# DC-DC_Bridge.net
KiCad netlist of a schematic drawn in Altium Designer
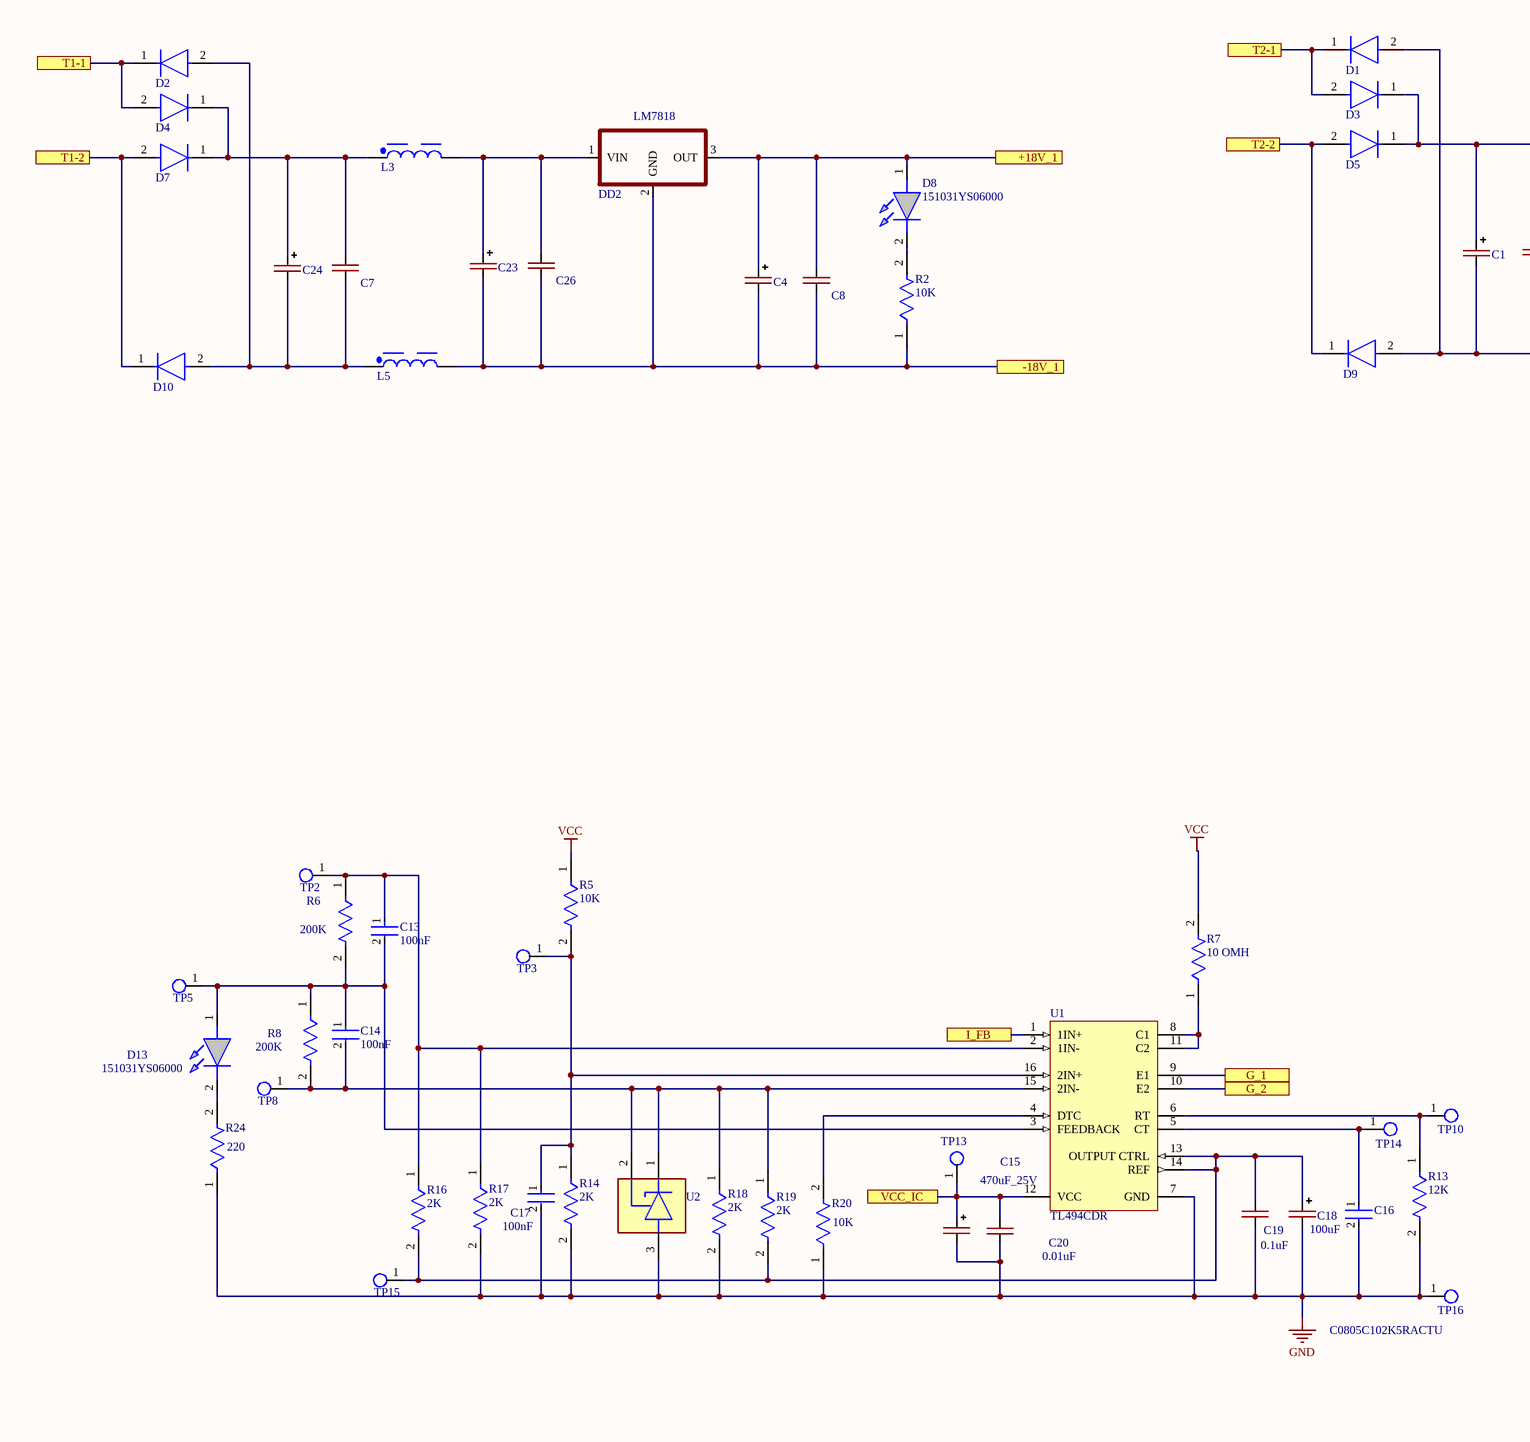
[diagram p0: DC-DC_Bridge.SchDoc, left]
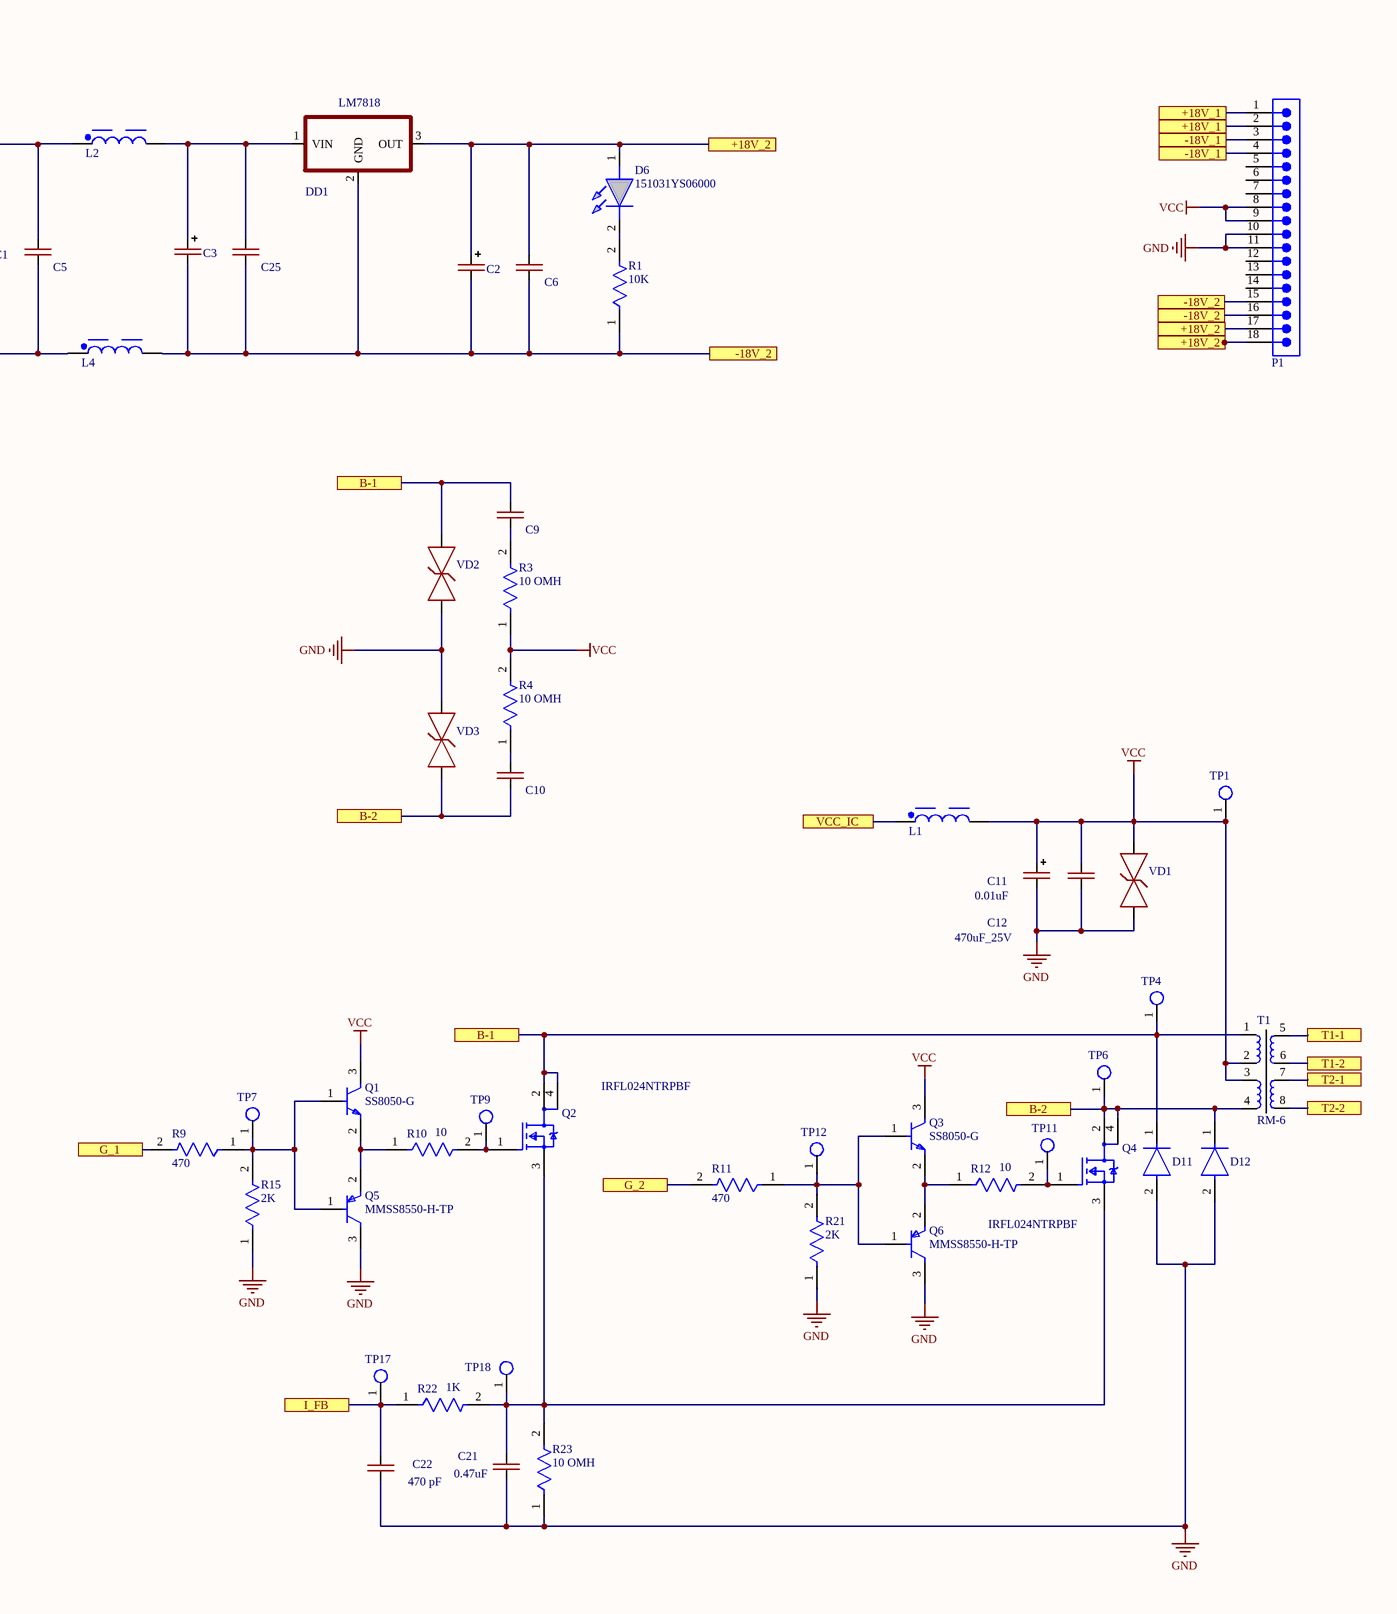
[diagram p1: DC-DC_Bridge.SchDoc, right]

(export (version "E")
  (design (tool "Eeschema 10.0.6"))
  (components
    (comp (ref "C1")
      (value "CAP-POLAR")
      (footprint "CAP_SMD_Size_G")
      (libsource (lib "PASSIVE_COMPONENTS") (part "CAP-POLAR"))
    )
    (comp (ref "C2")
      (value "CAP-POLAR")
      (footprint "CAP_SMD_Size_G")
      (libsource (lib "PASSIVE_COMPONENTS") (part "CAP-POLAR"))
    )
    (comp (ref "C3")
      (value "CAP-POLAR")
      (footprint "CAP_SMD_Size_G")
      (libsource (lib "PASSIVE_COMPONENTS") (part "CAP-POLAR"))
    )
    (comp (ref "C4")
      (value "CAP-POLAR")
      (footprint "CAP_SMD_Size_G")
      (libsource (lib "PASSIVE_COMPONENTS") (part "CAP-POLAR"))
    )
    (comp (ref "C5")
      (value "CAP-NON-POLAR")
      (footprint "CAP-0805")
      (libsource (lib "PASSIVE_COMPONENTS") (part "CAP-NON-POLAR"))
    )
    (comp (ref "C6")
      (value "CAP-NON-POLAR")
      (footprint "CAP-0805")
      (libsource (lib "PASSIVE_COMPONENTS") (part "CAP-NON-POLAR"))
    )
    (comp (ref "C7")
      (value "CAP-NON-POLAR")
      (footprint "CAP-0805")
      (libsource (lib "PASSIVE_COMPONENTS") (part "CAP-NON-POLAR"))
    )
    (comp (ref "C8")
      (value "CAP-NON-POLAR")
      (footprint "CAP-0805")
      (libsource (lib "PASSIVE_COMPONENTS") (part "CAP-NON-POLAR"))
    )
    (comp (ref "C9")
      (value "CAP-V")
      (footprint "CAP-V")
      (libsource (lib "PASSIVE_COMPONENTS") (part "CAP-V"))
    )
    (comp (ref "C10")
      (value "CAP-V")
      (footprint "CAP-V")
      (libsource (lib "PASSIVE_COMPONENTS") (part "CAP-V"))
    )
    (comp (ref "C11")
      (value "0.01uF")
      (footprint "CAP-0805")
      (libsource (lib "PASSIVE_COMPONENTS") (part "CAP-NON-POLAR"))
    )
    (comp (ref "C12")
      (value "470uF_25V")
      (footprint "CAPPOL-16x25")
      (libsource (lib "PASSIVE_COMPONENTS") (part "CAP-POLAR"))
    )
    (comp (ref "C13")
      (value "100nF")
      (footprint "FP-C0805C-DN-MFG")
      (description "CAP CER 10000PF 50V X7R 0805")
      (fields
        (field (name "MANUFACTURER PART NUMBER") "C0805C103J5RACTU")
        (field (name "MANUFACTURER") "KEMET")
      )
      (libsource (lib "Altium Content Vault") (part "b4654b650e69147ec39a6b967a45e02"))
    )
    (comp (ref "C14")
      (value "100nF")
      (footprint "FP-C0805C-DN-MFG")
      (description "CAP CER 10000PF 50V X7R 0805")
      (fields
        (field (name "MANUFACTURER PART NUMBER") "C0805C103J5RACTU")
        (field (name "MANUFACTURER") "KEMET")
      )
      (libsource (lib "Altium Content Vault") (part "b4654b650e69147ec39a6b967a45e02"))
    )
    (comp (ref "C15")
      (value "470uF_25V")
      (footprint "CAP_SMD_Size_G")
      (libsource (lib "PASSIVE_COMPONENTS") (part "CAP-POLAR"))
    )
    (comp (ref "C16")
      (value "C0805C102K5RACTU")
      (footprint "FP-C0805C-DN-MFG")
      (description "CAP CER 1000PF 50V X7R 0805")
      (fields
        (field (name "OCTOPART") "https://octopart.com/c0805c102k5ractu-kemet-93010")
        (field (name "TOLERANCE") "0.1")
      )
      (libsource (lib "Altium Content Vault") (part "b4654b650e69147ec39a6b967a45e02"))
    )
    (comp (ref "C17")
      (value "100nF")
      (footprint "FP-C0805C-DN-MFG")
      (description "CAP CER 10000PF 50V X7R 0805")
      (fields
        (field (name "MANUFACTURER PART NUMBER") "C0805C103J5RACTU")
        (field (name "MANUFACTURER") "KEMET")
      )
      (libsource (lib "Altium Content Vault") (part "b4654b650e69147ec39a6b967a45e02"))
    )
    (comp (ref "C18")
      (value "100uF")
      (footprint "CAP-TAN-D")
      (libsource (lib "PASSIVE_COMPONENTS") (part "CAP-POLAR"))
    )
    (comp (ref "C19")
      (value "0.1uF")
      (footprint "CAP-0805")
      (libsource (lib "PASSIVE_COMPONENTS") (part "CAP-NON-POLAR"))
    )
    (comp (ref "C20")
      (value "0.01uF")
      (footprint "CAP-0805")
      (libsource (lib "PASSIVE_COMPONENTS") (part "CAP-NON-POLAR"))
    )
    (comp (ref "C21")
      (value "0.47uF")
      (footprint "CAP-0805")
      (libsource (lib "PASSIVE_COMPONENTS") (part "CAP-NON-POLAR"))
    )
    (comp (ref "C22")
      (value "470 pF")
      (footprint "CAP-0805")
      (libsource (lib "PASSIVE_COMPONENTS") (part "CAP-NON-POLAR"))
    )
    (comp (ref "C23")
      (value "CAP-POLAR")
      (footprint "CAP_SMD_Size_G")
      (libsource (lib "PASSIVE_COMPONENTS") (part "CAP-POLAR"))
    )
    (comp (ref "C24")
      (value "CAP-POLAR")
      (footprint "CAP_SMD_Size_G")
      (libsource (lib "PASSIVE_COMPONENTS") (part "CAP-POLAR"))
    )
    (comp (ref "C25")
      (value "CAP-NON-POLAR")
      (footprint "CAP-0805")
      (libsource (lib "PASSIVE_COMPONENTS") (part "CAP-NON-POLAR"))
    )
    (comp (ref "C26")
      (value "CAP-NON-POLAR")
      (footprint "CAP-0805")
      (libsource (lib "PASSIVE_COMPONENTS") (part "CAP-NON-POLAR"))
    )
    (comp (ref "D1") (value "US1G") (footprint "DO-214AA") (libsource (lib "Diodes") (part "US1G")))
    (comp (ref "D2") (value "US1G") (footprint "DO-214AA") (libsource (lib "Diodes") (part "US1G")))
    (comp (ref "D3") (value "US1G") (footprint "DO-214AA") (libsource (lib "Diodes") (part "US1G")))
    (comp (ref "D4") (value "US1G") (footprint "DO-214AA") (libsource (lib "Diodes") (part "US1G")))
    (comp (ref "D5") (value "US1G") (footprint "DO-214AA") (libsource (lib "Diodes") (part "US1G")))
    (comp (ref "D6")
      (value "151031YS06000")
      (footprint "LED_RED")
      (description "WURTH ELEKTRONIK - 151031YS06000 - LED, Yellow, Through Hole, T-1 (3mm), 30 mA, 2 V, 590 nm")
      (fields (field (name "MOUSER PART NUMBER") "710-151031YS06000"))
      (libsource (lib "Optic-LED") (part "LED"))
    )
    (comp (ref "D7") (value "US1G") (footprint "DO-214AA") (libsource (lib "Diodes") (part "US1G")))
    (comp (ref "D8")
      (value "151031YS06000")
      (footprint "LED_RED")
      (description "WURTH ELEKTRONIK - 151031YS06000 - LED, Yellow, Through Hole, T-1 (3mm), 30 mA, 2 V, 590 nm")
      (fields (field (name "MOUSER PART NUMBER") "710-151031YS06000"))
      (libsource (lib "Optic-LED") (part "LED"))
    )
    (comp (ref "D9") (value "US1G") (footprint "DO-214AA") (libsource (lib "Diodes") (part "US1G")))
    (comp (ref "D10") (value "US1G") (footprint "DO-214AA") (libsource (lib "Diodes") (part "US1G")))
    (comp (ref "D11") (value "US1G") (footprint "DO-214AA") (libsource (lib "Diodes") (part "US1G")))
    (comp (ref "D12") (value "US1G") (footprint "DO-214AA") (libsource (lib "Diodes") (part "US1G")))
    (comp (ref "D13")
      (value "151031YS06000")
      (footprint "LED_RED")
      (description "WURTH ELEKTRONIK - 151031YS06000 - LED, Yellow, Through Hole, T-1 (3mm), 30 mA, 2 V, 590 nm")
      (fields (field (name "MOUSER PART NUMBER") "710-151031YS06000"))
      (libsource (lib "Optic-LED") (part "LED"))
    )
    (comp (ref "DD1")
      (value "LM7818")
      (footprint "TO-252")
      (libsource (lib "LM7818__TO-252") (part "LM7818"))
    )
    (comp (ref "DD2")
      (value "LM7818")
      (footprint "TO-252")
      (libsource (lib "LM7818__TO-252") (part "LM7818"))
    )
    (comp (ref "L1")
      (value "390µH, 0.38A")
      (footprint "WE-PD2_7850")
      (description "WE-PD2 SMT Power Inductor, size 7850, 390µH, 0.38A, 1.77Ω")
      (fields
        (field (name "MANUFACTURER PART NUMBER") "744775239")
        (field (name "MANUFACTURER") "Wurth Elektronik")
      )
      (libsource (lib "WE-PD2 (rev22d)") (part "744775239"))
    )
    (comp (ref "L2")
      (value "390µH, 0.38A")
      (footprint "WE-PD2_7850")
      (description "WE-PD2 SMT Power Inductor, size 7850, 390µH, 0.38A, 1.77Ω")
      (fields
        (field (name "MANUFACTURER PART NUMBER") "744775239")
        (field (name "MANUFACTURER") "Wurth Elektronik")
      )
      (libsource (lib "WE-PD2 (rev22d)") (part "744775239"))
    )
    (comp (ref "L3")
      (value "390µH, 0.38A")
      (footprint "WE-PD2_7850")
      (description "WE-PD2 SMT Power Inductor, size 7850, 390µH, 0.38A, 1.77Ω")
      (fields
        (field (name "MANUFACTURER PART NUMBER") "744775239")
        (field (name "MANUFACTURER") "Wurth Elektronik")
      )
      (libsource (lib "WE-PD2 (rev22d)") (part "744775239"))
    )
    (comp (ref "L4")
      (value "390µH, 0.38A")
      (footprint "WE-PD2_7850")
      (description "WE-PD2 SMT Power Inductor, size 7850, 390µH, 0.38A, 1.77Ω")
      (fields
        (field (name "MANUFACTURER PART NUMBER") "744775239")
        (field (name "MANUFACTURER") "Wurth Elektronik")
      )
      (libsource (lib "WE-PD2 (rev22d)") (part "744775239"))
    )
    (comp (ref "L5")
      (value "390µH, 0.38A")
      (footprint "WE-PD2_7850")
      (description "WE-PD2 SMT Power Inductor, size 7850, 390µH, 0.38A, 1.77Ω")
      (fields
        (field (name "MANUFACTURER PART NUMBER") "744775239")
        (field (name "MANUFACTURER") "Wurth Elektronik")
      )
      (libsource (lib "WE-PD2 (rev22d)") (part "744775239"))
    )
    (comp (ref "P1")
      (value "61301811021")
      (footprint "61301811021")
      (description "WR-PHD Pin Header, THT, Angled, pitch 2.54mm, 1 Row, 18P")
      (fields (field (name "MANUFACTURER") "Wurth Elektronik"))
      (libsource (lib "Altium_WR-PHD (rev22b)") (part "61301811021"))
    )
    (comp (ref "Q1")
      (value "SS8050-G")
      (footprint "FP-SS8050-G-MFG")
      (description "NPN TRANSISTOR 1.5A 40V SOT-23 R")
      (libsource (lib "Altium Content Vault") (part "2a1388f82443b098dcd57d24ac7632d"))
    )
    (comp (ref "Q2")
      (value "IRFL024NTRPBF")
      (footprint "FP-PG-SOT223-3-IPC_B")
      (description "MOSFET N-CH 55V 2.8A SOT223")
      (libsource (lib "Altium Content Vault") (part "7f70c8421781a2c4d0598199639518f"))
    )
    (comp (ref "Q3")
      (value "SS8050-G")
      (footprint "FP-SS8050-G-MFG")
      (description "NPN TRANSISTOR 1.5A 40V SOT-23 R")
      (libsource (lib "Altium Content Vault") (part "2a1388f82443b098dcd57d24ac7632d"))
    )
    (comp (ref "Q4")
      (value "IRFL024NTRPBF")
      (footprint "FP-PG-SOT223-3-IPC_B")
      (description "MOSFET N-CH 55V 2.8A SOT223")
      (libsource (lib "Altium Content Vault") (part "7f70c8421781a2c4d0598199639518f"))
    )
    (comp (ref "Q5")
      (value "MMSS8550-H-TP")
      (footprint "FP-SOT-23-IPC_B")
      (description "TRANS PNP 25V 1.5A SOT23")
      (libsource (lib "Altium Content Vault") (part "0e8486ed3b47d9c69b8404ba87cf0f7"))
    )
    (comp (ref "Q6")
      (value "MMSS8550-H-TP")
      (footprint "FP-SOT-23-IPC_B")
      (description "TRANS PNP 25V 1.5A SOT23")
      (libsource (lib "Altium Content Vault") (part "0e8486ed3b47d9c69b8404ba87cf0f7"))
    )
    (comp (ref "R1")
      (value "10K")
      (footprint "RES-0805")
      (libsource (lib "PASSIVE_COMPONENTS") (part "RES-CONST"))
    )
    (comp (ref "R2")
      (value "10K")
      (footprint "RES-0805")
      (libsource (lib "PASSIVE_COMPONENTS") (part "RES-CONST"))
    )
    (comp (ref "R3")
      (value "10 OMH")
      (footprint "RES-1206")
      (libsource (lib "PASSIVE_COMPONENTS") (part "RES-CONST"))
    )
    (comp (ref "R4")
      (value "10 OMH")
      (footprint "RES-1206")
      (libsource (lib "PASSIVE_COMPONENTS") (part "RES-CONST"))
    )
    (comp (ref "R5")
      (value "10K")
      (footprint "FP-CRCW0805-e3-MFG")
      (description "RES Thick Film, 2kΩ, 1%, 0.125W, 100ppm/°C, 0805")
      (fields (field (name "TOLERANCE") "1%"))
      (libsource (lib "Pasive_components") (part "CMP-2001-04908-2"))
    )
    (comp (ref "R6")
      (value "200K")
      (footprint "FP-CRCW0805-e3-MFG")
      (description "RES Thick Film, 2kΩ, 1%, 0.125W, 100ppm/°C, 0805")
      (fields (field (name "TOLERANCE") "1%"))
      (libsource (lib "Pasive_components") (part "CMP-2001-04908-2"))
    )
    (comp (ref "R7")
      (value "10 OMH")
      (footprint "RES-1206")
      (libsource (lib "PASSIVE_COMPONENTS") (part "RES-CONST"))
    )
    (comp (ref "R8")
      (value "200K")
      (footprint "FP-CRCW0805-e3-MFG")
      (description "RES Thick Film, 2kΩ, 1%, 0.125W, 100ppm/°C, 0805")
      (fields (field (name "TOLERANCE") "1%"))
      (libsource (lib "Pasive_components") (part "CMP-2001-04908-2"))
    )
    (comp (ref "R9")
      (value "470")
      (footprint "RES-0805")
      (libsource (lib "PASSIVE_COMPONENTS") (part "RES-CONST"))
    )
    (comp (ref "R10")
      (value "10")
      (footprint "RES-0805")
      (libsource (lib "PASSIVE_COMPONENTS") (part "RES-CONST"))
    )
    (comp (ref "R11")
      (value "470")
      (footprint "RES-0805")
      (libsource (lib "PASSIVE_COMPONENTS") (part "RES-CONST"))
    )
    (comp (ref "R12")
      (value "10")
      (footprint "RES-0805")
      (libsource (lib "PASSIVE_COMPONENTS") (part "RES-CONST"))
    )
    (comp (ref "R13")
      (value "12K")
      (footprint "FP-CRCW0805-e3-MFG")
      (description "RES Thick Film, 12kΩ, 1%, 0.125W, 100ppm/°C, 0805")
      (fields (field (name "TOLERANCE") "1%"))
      (libsource (lib "Pasive_components") (part "CMP-2001-04908-2"))
    )
    (comp (ref "R14")
      (value "2K")
      (footprint "FP-CRCW0805-e3-MFG")
      (description "RES Thick Film, 2kΩ, 1%, 0.125W, 100ppm/°C, 0805")
      (fields (field (name "TOLERANCE") "1%"))
      (libsource (lib "Pasive_components") (part "CMP-2001-04908-2"))
    )
    (comp (ref "R15")
      (value "2K")
      (footprint "RES-0805")
      (libsource (lib "PASSIVE_COMPONENTS") (part "RES-CONST"))
    )
    (comp (ref "R16")
      (value "2K")
      (footprint "FP-CRCW0805-e3-MFG")
      (description "RES Thick Film, 2kΩ, 1%, 0.125W, 100ppm/°C, 0805")
      (fields (field (name "TOLERANCE") "1%"))
      (libsource (lib "Pasive_components") (part "CMP-2001-04908-2"))
    )
    (comp (ref "R17")
      (value "2K")
      (footprint "FP-CRCW0805-e3-MFG")
      (description "RES Thick Film, 82kΩ, 1%, 0.125W, 100ppm/°C, 0805")
      (fields (field (name "TOLERANCE") "1%"))
      (libsource (lib "Pasive_components") (part "CMP-2001-04908-2"))
    )
    (comp (ref "R18")
      (value "2K")
      (footprint "FP-CRCW0805-e3-MFG")
      (description "RES Thick Film, 2kΩ, 1%, 0.125W, 100ppm/°C, 0805")
      (fields (field (name "TOLERANCE") "1%"))
      (libsource (lib "Pasive_components") (part "CMP-2001-04908-2"))
    )
    (comp (ref "R19")
      (value "2K")
      (footprint "FP-CRCW0805-e3-MFG")
      (description "RES Thick Film, 2kΩ, 1%, 0.125W, 100ppm/°C, 0805")
      (fields (field (name "TOLERANCE") "1%"))
      (libsource (lib "Pasive_components") (part "CMP-2001-04908-2"))
    )
    (comp (ref "R20")
      (value "10K")
      (footprint "RES-0805")
      (libsource (lib "PASSIVE_COMPONENTS") (part "RES-CONST"))
    )
    (comp (ref "R21")
      (value "2K")
      (footprint "RES-0805")
      (libsource (lib "PASSIVE_COMPONENTS") (part "RES-CONST"))
    )
    (comp (ref "R22")
      (value "1K")
      (footprint "RES-0805")
      (libsource (lib "PASSIVE_COMPONENTS") (part "RES-CONST"))
    )
    (comp (ref "R23")
      (value "10 OMH")
      (footprint "RES-2512")
      (libsource (lib "PASSIVE_COMPONENTS") (part "RES-CONST"))
    )
    (comp (ref "R24")
      (value "220")
      (footprint "RES-0805")
      (libsource (lib "PASSIVE_COMPONENTS") (part "RES-CONST"))
    )
    (comp (ref "T1")
      (value "RM-6")
      (footprint "TRANS_RM6")
      (libsource (lib "Transformers") (part "RM_6_12-12-18-18"))
    )
    (comp (ref "TP1")
      (value "~")
      (footprint "Test_Point")
      (description "Test_Point")
      (libsource (lib "Connectors") (part "TP_PCB?"))
    )
    (comp (ref "TP2")
      (value "Test_Point_PCB")
      (footprint "Test_Point")
      (description "Test_Point")
      (libsource (lib "Test_Point") (part "TP_PCB?"))
    )
    (comp (ref "TP3")
      (value "Test_Point_PCB")
      (footprint "Test_Point")
      (description "Test_Point")
      (libsource (lib "Test_Point") (part "TP_PCB?"))
    )
    (comp (ref "TP4")
      (value "~")
      (footprint "Test_Point")
      (description "Test_Point")
      (libsource (lib "Connectors") (part "TP_PCB?"))
    )
    (comp (ref "TP5")
      (value "Test_Point_PCB")
      (footprint "Test_Point")
      (description "Test_Point")
      (libsource (lib "Test_Point") (part "TP_PCB?"))
    )
    (comp (ref "TP6")
      (value "~")
      (footprint "Test_Point")
      (description "Test_Point")
      (libsource (lib "Connectors") (part "TP_PCB?"))
    )
    (comp (ref "TP7")
      (value "~")
      (footprint "Test_Point")
      (description "Test_Point")
      (libsource (lib "Connectors") (part "TP_PCB?"))
    )
    (comp (ref "TP8")
      (value "~")
      (footprint "Test_Point")
      (description "Test_Point")
      (libsource (lib "Connectors") (part "TP_PCB?"))
    )
    (comp (ref "TP9")
      (value "~")
      (footprint "Test_Point")
      (description "Test_Point")
      (libsource (lib "Connectors") (part "TP_PCB?"))
    )
    (comp (ref "TP10")
      (value "~")
      (footprint "Test_Point")
      (description "Test_Point")
      (libsource (lib "Connectors") (part "TP_PCB?"))
    )
    (comp (ref "TP11")
      (value "~")
      (footprint "Test_Point")
      (description "Test_Point")
      (libsource (lib "Connectors") (part "TP_PCB?"))
    )
    (comp (ref "TP12")
      (value "~")
      (footprint "Test_Point")
      (description "Test_Point")
      (libsource (lib "Connectors") (part "TP_PCB?"))
    )
    (comp (ref "TP13")
      (value "~")
      (footprint "Test_Point")
      (description "Test_Point")
      (libsource (lib "Connectors") (part "TP_PCB?"))
    )
    (comp (ref "TP14")
      (value "Test_Point_PCB")
      (footprint "Test_Point")
      (description "Test_Point")
      (libsource (lib "Test_Point") (part "TP_PCB?"))
    )
    (comp (ref "TP15")
      (value "Test_Point_PCB")
      (footprint "Test_Point")
      (description "Test_Point")
      (libsource (lib "Test_Point") (part "TP_PCB?"))
    )
    (comp (ref "TP16")
      (value "~")
      (footprint "Test_Point")
      (description "Test_Point")
      (libsource (lib "Connectors") (part "TP_PCB?"))
    )
    (comp (ref "TP17")
      (value "~")
      (footprint "Test_Point")
      (description "Test_Point")
      (libsource (lib "Connectors") (part "TP_PCB?"))
    )
    (comp (ref "TP18")
      (value "~")
      (footprint "Test_Point")
      (description "Test_Point")
      (libsource (lib "Connectors") (part "TP_PCB?"))
    )
    (comp (ref "U1")
      (value "TL494CDR")
      (footprint "D0016A_N")
      (fields (field (name "MANUFACTURER") "Texas Instruments"))
      (libsource (lib "Altium Content Vault") (part "TI-494D16"))
    )
    (comp (ref "U2")
      (value "TL431")
      (footprint "TL431_SOT-23-3(A)")
      (description "TL431_SOT-23-3")
      (libsource (lib "Diodes") (part "TL431_SOT-23-3"))
    )
    (comp (ref "VD1")
      (value "Suppressor")
      (footprint "DO-214AA")
      (libsource (lib "Diodes") (part "Suppressor"))
    )
    (comp (ref "VD2")
      (value "Suppressor")
      (footprint "P6KE350CA")
      (libsource (lib "Diodes") (part "Suppressor"))
    )
    (comp (ref "VD3")
      (value "Suppressor")
      (footprint "P6KE350CA")
      (libsource (lib "Diodes") (part "Suppressor"))
    )
  )
  (nets
    (net (code "1") (name "/+18V_1") (class "Default")
      (node (ref "C4") (pin "1") (pinfunction "+_1") (pintype "passive"))
      (node (ref "C8") (pin "2") (pinfunction "2_2") (pintype "passive"))
      (node (ref "D8") (pin "1") (pinfunction "A_1") (pintype "passive"))
      (node (ref "DD2") (pin "3") (pinfunction "OUT_3") (pintype "passive"))
      (node (ref "P1") (pin "1") (pinfunction "1_1") (pintype "passive"))
      (node (ref "P1") (pin "2") (pinfunction "2_2") (pintype "passive"))
    )
    (net (code "2") (name "/+18V_2") (class "Default")
      (node (ref "C2") (pin "1") (pinfunction "+_1") (pintype "passive"))
      (node (ref "C6") (pin "2") (pinfunction "2_2") (pintype "passive"))
      (node (ref "D6") (pin "1") (pinfunction "A_1") (pintype "passive"))
      (node (ref "DD1") (pin "3") (pinfunction "OUT_3") (pintype "passive"))
      (node (ref "P1") (pin "17") (pinfunction "17_17") (pintype "passive"))
      (node (ref "P1") (pin "18") (pinfunction "18_18") (pintype "passive"))
    )
    (net (code "3") (name "/-18V_1") (class "Default")
      (node (ref "C23") (pin "2") (pinfunction "-_2") (pintype "passive"))
      (node (ref "C26") (pin "1") (pinfunction "1_1") (pintype "passive"))
      (node (ref "C4") (pin "2") (pinfunction "-_2") (pintype "passive"))
      (node (ref "C8") (pin "1") (pinfunction "1_1") (pintype "passive"))
      (node (ref "DD2") (pin "2") (pinfunction "GND_2") (pintype "passive"))
      (node (ref "L5") (pin "2") (pinfunction "2_2") (pintype "passive"))
      (node (ref "P1") (pin "3") (pinfunction "3_3") (pintype "passive"))
      (node (ref "P1") (pin "4") (pinfunction "4_4") (pintype "passive"))
      (node (ref "R2") (pin "1") (pinfunction "1_1") (pintype "passive"))
    )
    (net (code "4") (name "/-18V_2") (class "Default")
      (node (ref "C2") (pin "2") (pinfunction "-_2") (pintype "passive"))
      (node (ref "C25") (pin "1") (pinfunction "1_1") (pintype "passive"))
      (node (ref "C3") (pin "2") (pinfunction "-_2") (pintype "passive"))
      (node (ref "C6") (pin "1") (pinfunction "1_1") (pintype "passive"))
      (node (ref "DD1") (pin "2") (pinfunction "GND_2") (pintype "passive"))
      (node (ref "L4") (pin "2") (pinfunction "2_2") (pintype "passive"))
      (node (ref "P1") (pin "15") (pinfunction "15_15") (pintype "passive"))
      (node (ref "P1") (pin "16") (pinfunction "16_16") (pintype "passive"))
      (node (ref "R1") (pin "1") (pinfunction "1_1") (pintype "passive"))
    )
    (net (code "5") (name "/B-1") (class "Default")
      (node (ref "C9") (pin "2") (pinfunction "2_2") (pintype "passive"))
      (node (ref "D11") (pin "1") (pinfunction "C_1") (pintype "passive"))
      (node (ref "Q2") (pin "2") (pinfunction "D_2") (pintype "passive"))
      (node (ref "Q2") (pin "4") (pinfunction "D_4") (pintype "passive"))
      (node (ref "T1") (pin "1") (pinfunction "1_1") (pintype "passive"))
      (node (ref "TP4") (pin "1") (pinfunction "G9_1") (pintype "passive"))
      (node (ref "VD2") (pin "2") (pinfunction "A_2") (pintype "passive"))
    )
    (net (code "6") (name "/B-2") (class "Default")
      (node (ref "C10") (pin "1") (pinfunction "1_1") (pintype "passive"))
      (node (ref "D12") (pin "1") (pinfunction "C_1") (pintype "passive"))
      (node (ref "Q4") (pin "2") (pinfunction "D_2") (pintype "passive"))
      (node (ref "Q4") (pin "4") (pinfunction "D_4") (pintype "passive"))
      (node (ref "T1") (pin "4") (pinfunction "4_4") (pintype "passive"))
      (node (ref "TP6") (pin "1") (pinfunction "G9_1") (pintype "passive"))
      (node (ref "VD3") (pin "1") (pinfunction "C_1") (pintype "passive"))
    )
    (net (code "7") (name "/G_1") (class "Default")
      (node (ref "R9") (pin "2") (pinfunction "2_2") (pintype "passive"))
      (node (ref "U1") (pin "9") (pinfunction "E1_9") (pintype "passive"))
    )
    (net (code "8") (name "/G_2") (class "Default")
      (node (ref "R11") (pin "2") (pinfunction "2_2") (pintype "passive"))
      (node (ref "U1") (pin "10") (pinfunction "E2_10") (pintype "passive"))
    )
    (net (code "9") (name "/I_FB") (class "Default")
      (node (ref "C22") (pin "2") (pinfunction "2_2") (pintype "passive"))
      (node (ref "R22") (pin "1") (pinfunction "1_1") (pintype "passive"))
      (node (ref "TP17") (pin "1") (pinfunction "G9_1") (pintype "passive"))
      (node (ref "U1") (pin "1") (pinfunction "1IN+_1") (pintype "input"))
    )
    (net (code "10") (name "/T1-1") (class "Default")
      (node (ref "D2") (pin "1") (pinfunction "C_1") (pintype "passive"))
      (node (ref "D4") (pin "2") (pinfunction "A_2") (pintype "passive"))
      (node (ref "T1") (pin "5") (pinfunction "5_5") (pintype "passive"))
    )
    (net (code "11") (name "/T1-2") (class "Default")
      (node (ref "D10") (pin "1") (pinfunction "C_1") (pintype "passive"))
      (node (ref "D7") (pin "2") (pinfunction "A_2") (pintype "passive"))
      (node (ref "T1") (pin "6") (pinfunction "6_6") (pintype "passive"))
    )
    (net (code "12") (name "/T2-1") (class "Default")
      (node (ref "D1") (pin "1") (pinfunction "C_1") (pintype "passive"))
      (node (ref "D3") (pin "2") (pinfunction "A_2") (pintype "passive"))
      (node (ref "T1") (pin "7") (pinfunction "7_7") (pintype "passive"))
    )
    (net (code "13") (name "/T2-2") (class "Default")
      (node (ref "D5") (pin "2") (pinfunction "A_2") (pintype "passive"))
      (node (ref "D9") (pin "1") (pinfunction "C_1") (pintype "passive"))
      (node (ref "T1") (pin "8") (pinfunction "8_8") (pintype "passive"))
    )
    (net (code "14") (name "/VCC_IC") (class "Default")
      (node (ref "C15") (pin "1") (pinfunction "+_1") (pintype "passive"))
      (node (ref "C20") (pin "2") (pinfunction "2_2") (pintype "passive"))
      (node (ref "L1") (pin "1") (pinfunction "1_1") (pintype "passive"))
      (node (ref "TP13") (pin "1") (pinfunction "G9_1") (pintype "passive"))
      (node (ref "U1") (pin "12") (pinfunction "VCC_12") (pintype "power_in"))
    )
    (net (code "15") (name "GND") (class "Default")
      (node (ref "C11") (pin "1") (pinfunction "1_1") (pintype "passive"))
      (node (ref "C12") (pin "2") (pinfunction "-_2") (pintype "passive"))
      (node (ref "C15") (pin "2") (pinfunction "-_2") (pintype "passive"))
      (node (ref "C16") (pin "2") (pinfunction "2_2") (pintype "passive"))
      (node (ref "C17") (pin "2") (pinfunction "2_2") (pintype "passive"))
      (node (ref "C18") (pin "2") (pinfunction "-_2") (pintype "passive"))
      (node (ref "C19") (pin "1") (pinfunction "1_1") (pintype "passive"))
      (node (ref "C20") (pin "1") (pinfunction "1_1") (pintype "passive"))
      (node (ref "C21") (pin "1") (pinfunction "1_1") (pintype "passive"))
      (node (ref "C22") (pin "1") (pinfunction "1_1") (pintype "passive"))
      (node (ref "D11") (pin "2") (pinfunction "A_2") (pintype "passive"))
      (node (ref "D12") (pin "2") (pinfunction "A_2") (pintype "passive"))
      (node (ref "P1") (pin "10") (pinfunction "10_10") (pintype "passive"))
      (node (ref "P1") (pin "11") (pinfunction "11_11") (pintype "passive"))
      (node (ref "Q5") (pin "3") (pinfunction "C_3") (pintype "passive"))
      (node (ref "Q6") (pin "3") (pinfunction "C_3") (pintype "passive"))
      (node (ref "R13") (pin "2") (pinfunction "2_2") (pintype "passive"))
      (node (ref "R14") (pin "2") (pinfunction "2_2") (pintype "passive"))
      (node (ref "R15") (pin "1") (pinfunction "1_1") (pintype "passive"))
      (node (ref "R17") (pin "2") (pinfunction "2_2") (pintype "passive"))
      (node (ref "R18") (pin "2") (pinfunction "2_2") (pintype "passive"))
      (node (ref "R20") (pin "1") (pinfunction "1_1") (pintype "passive"))
      (node (ref "R21") (pin "1") (pinfunction "1_1") (pintype "passive"))
      (node (ref "R23") (pin "1") (pinfunction "1_1") (pintype "passive"))
      (node (ref "R24") (pin "1") (pinfunction "1_1") (pintype "passive"))
      (node (ref "TP16") (pin "1") (pinfunction "G9_1") (pintype "passive"))
      (node (ref "U1") (pin "7") (pinfunction "GND_7") (pintype "power_in"))
      (node (ref "U2") (pin "3") (pinfunction "A_3") (pintype "passive"))
      (node (ref "VD1") (pin "1") (pinfunction "C_1") (pintype "passive"))
      (node (ref "VD2") (pin "1") (pinfunction "C_1") (pintype "passive"))
      (node (ref "VD3") (pin "2") (pinfunction "A_2") (pintype "passive"))
    )
    (net (code "16") (name "Net-(C1-+)") (class "Default")
      (node (ref "C1") (pin "1") (pinfunction "+_1") (pintype "passive"))
      (node (ref "C5") (pin "2") (pinfunction "2_2") (pintype "passive"))
      (node (ref "D3") (pin "1") (pinfunction "C_1") (pintype "passive"))
      (node (ref "D5") (pin "1") (pinfunction "C_1") (pintype "passive"))
      (node (ref "L2") (pin "1") (pinfunction "1_1") (pintype "passive"))
    )
    (net (code "17") (name "Net-(C1--)") (class "Default")
      (node (ref "C1") (pin "2") (pinfunction "-_2") (pintype "passive"))
      (node (ref "C5") (pin "1") (pinfunction "1_1") (pintype "passive"))
      (node (ref "D1") (pin "2") (pinfunction "A_2") (pintype "passive"))
      (node (ref "D9") (pin "2") (pinfunction "A_2") (pintype "passive"))
      (node (ref "L4") (pin "1") (pinfunction "1_1") (pintype "passive"))
    )
    (net (code "18") (name "Net-(C3-+)") (class "Default")
      (node (ref "C25") (pin "2") (pinfunction "2_2") (pintype "passive"))
      (node (ref "C3") (pin "1") (pinfunction "+_1") (pintype "passive"))
      (node (ref "DD1") (pin "1") (pinfunction "VIN_1") (pintype "passive"))
      (node (ref "L2") (pin "2") (pinfunction "2_2") (pintype "passive"))
    )
    (net (code "19") (name "Net-(C9-Pad1)") (class "Default")
      (node (ref "C9") (pin "1") (pinfunction "1_1") (pintype "passive"))
      (node (ref "R3") (pin "2") (pinfunction "2_2") (pintype "passive"))
    )
    (net (code "20") (name "Net-(C10-Pad2)") (class "Default")
      (node (ref "C10") (pin "2") (pinfunction "2_2") (pintype "passive"))
      (node (ref "R4") (pin "1") (pinfunction "1_1") (pintype "passive"))
    )
    (net (code "21") (name "Net-(C18-+)") (class "Default")
      (node (ref "C18") (pin "1") (pinfunction "+_1") (pintype "passive"))
      (node (ref "C19") (pin "2") (pinfunction "2_2") (pintype "passive"))
      (node (ref "R16") (pin "2") (pinfunction "2_2") (pintype "passive"))
      (node (ref "R19") (pin "2") (pinfunction "2_2") (pintype "passive"))
      (node (ref "TP15") (pin "1") (pinfunction "G9_1") (pintype "passive"))
      (node (ref "U1") (pin "13") (pinfunction "OUTPUT_CTRL_13") (pintype "input"))
      (node (ref "U1") (pin "14") (pinfunction "REF_14") (pintype "output"))
    )
    (net (code "22") (name "Net-(C23-+)") (class "Default")
      (node (ref "C23") (pin "1") (pinfunction "+_1") (pintype "passive"))
      (node (ref "C26") (pin "2") (pinfunction "2_2") (pintype "passive"))
      (node (ref "DD2") (pin "1") (pinfunction "VIN_1") (pintype "passive"))
      (node (ref "L3") (pin "2") (pinfunction "2_2") (pintype "passive"))
    )
    (net (code "23") (name "Net-(C24-+)") (class "Default")
      (node (ref "C24") (pin "1") (pinfunction "+_1") (pintype "passive"))
      (node (ref "C7") (pin "2") (pinfunction "2_2") (pintype "passive"))
      (node (ref "D4") (pin "1") (pinfunction "C_1") (pintype "passive"))
      (node (ref "D7") (pin "1") (pinfunction "C_1") (pintype "passive"))
      (node (ref "L3") (pin "1") (pinfunction "1_1") (pintype "passive"))
    )
    (net (code "24") (name "Net-(C24--)") (class "Default")
      (node (ref "C24") (pin "2") (pinfunction "-_2") (pintype "passive"))
      (node (ref "C7") (pin "1") (pinfunction "1_1") (pintype "passive"))
      (node (ref "D10") (pin "2") (pinfunction "A_2") (pintype "passive"))
      (node (ref "D2") (pin "2") (pinfunction "A_2") (pintype "passive"))
      (node (ref "L5") (pin "1") (pinfunction "1_1") (pintype "passive"))
    )
    (net (code "25") (name "Net-(D6-K)") (class "Default")
      (node (ref "D6") (pin "2") (pinfunction "K_2") (pintype "passive"))
      (node (ref "R1") (pin "2") (pinfunction "2_2") (pintype "passive"))
    )
    (net (code "26") (name "Net-(D8-K)") (class "Default")
      (node (ref "D8") (pin "2") (pinfunction "K_2") (pintype "passive"))
      (node (ref "R2") (pin "2") (pinfunction "2_2") (pintype "passive"))
    )
    (net (code "27") (name "Net-(D13-A)") (class "Default")
      (node (ref "C13") (pin "2") (pinfunction "2_2") (pintype "passive"))
      (node (ref "C14") (pin "1") (pinfunction "1_1") (pintype "passive"))
      (node (ref "D13") (pin "1") (pinfunction "A_1") (pintype "passive"))
      (node (ref "R6") (pin "2") (pinfunction "2_2") (pintype "passive"))
      (node (ref "R8") (pin "1") (pinfunction "1_1") (pintype "passive"))
      (node (ref "TP5") (pin "1") (pinfunction "G9_1") (pintype "passive"))
      (node (ref "U1") (pin "3") (pinfunction "FEEDBACK_3") (pintype "input"))
    )
    (net (code "28") (name "Net-(D13-K)") (class "Default")
      (node (ref "D13") (pin "2") (pinfunction "K_2") (pintype "passive"))
      (node (ref "R24") (pin "2") (pinfunction "2_2") (pintype "passive"))
    )
    (net (code "29") (name "Net-(Q1-B)") (class "Default")
      (node (ref "Q1") (pin "1") (pinfunction "B_1") (pintype "passive"))
      (node (ref "Q5") (pin "1") (pinfunction "B_1") (pintype "passive"))
      (node (ref "R15") (pin "2") (pinfunction "2_2") (pintype "passive"))
      (node (ref "R9") (pin "1") (pinfunction "1_1") (pintype "passive"))
      (node (ref "TP7") (pin "1") (pinfunction "G9_1") (pintype "passive"))
    )
    (net (code "30") (name "Net-(Q1-E)") (class "Default")
      (node (ref "Q1") (pin "2") (pinfunction "E_2") (pintype "passive"))
      (node (ref "Q5") (pin "2") (pinfunction "E_2") (pintype "passive"))
      (node (ref "R10") (pin "1") (pinfunction "1_1") (pintype "passive"))
    )
    (net (code "31") (name "Net-(Q2-G)") (class "Default")
      (node (ref "Q2") (pin "1") (pinfunction "G_1") (pintype "passive"))
      (node (ref "R10") (pin "2") (pinfunction "2_2") (pintype "passive"))
      (node (ref "TP9") (pin "1") (pinfunction "G9_1") (pintype "passive"))
    )
    (net (code "32") (name "Net-(Q2-S)") (class "Default")
      (node (ref "C21") (pin "2") (pinfunction "2_2") (pintype "passive"))
      (node (ref "Q2") (pin "3") (pinfunction "S_3") (pintype "passive"))
      (node (ref "Q4") (pin "3") (pinfunction "S_3") (pintype "passive"))
      (node (ref "R22") (pin "2") (pinfunction "2_2") (pintype "passive"))
      (node (ref "R23") (pin "2") (pinfunction "2_2") (pintype "passive"))
      (node (ref "TP18") (pin "1") (pinfunction "G9_1") (pintype "passive"))
    )
    (net (code "33") (name "Net-(Q3-B)") (class "Default")
      (node (ref "Q3") (pin "1") (pinfunction "B_1") (pintype "passive"))
      (node (ref "Q6") (pin "1") (pinfunction "B_1") (pintype "passive"))
      (node (ref "R11") (pin "1") (pinfunction "1_1") (pintype "passive"))
      (node (ref "R21") (pin "2") (pinfunction "2_2") (pintype "passive"))
      (node (ref "TP12") (pin "1") (pinfunction "G9_1") (pintype "passive"))
    )
    (net (code "34") (name "Net-(Q3-E)") (class "Default")
      (node (ref "Q3") (pin "2") (pinfunction "E_2") (pintype "passive"))
      (node (ref "Q6") (pin "2") (pinfunction "E_2") (pintype "passive"))
      (node (ref "R12") (pin "1") (pinfunction "1_1") (pintype "passive"))
    )
    (net (code "35") (name "Net-(Q4-G)") (class "Default")
      (node (ref "Q4") (pin "1") (pinfunction "G_1") (pintype "passive"))
      (node (ref "R12") (pin "2") (pinfunction "2_2") (pintype "passive"))
      (node (ref "TP11") (pin "1") (pinfunction "G9_1") (pintype "passive"))
    )
    (net (code "36") (name "Net-(TP2-G9)") (class "Default")
      (node (ref "C13") (pin "1") (pinfunction "1_1") (pintype "passive"))
      (node (ref "R16") (pin "1") (pinfunction "1_1") (pintype "passive"))
      (node (ref "R17") (pin "1") (pinfunction "1_1") (pintype "passive"))
      (node (ref "R6") (pin "1") (pinfunction "1_1") (pintype "passive"))
      (node (ref "TP2") (pin "1") (pinfunction "G9_1") (pintype "passive"))
      (node (ref "U1") (pin "2") (pinfunction "1IN-_2") (pintype "input"))
    )
    (net (code "37") (name "Net-(TP3-G9)") (class "Default")
      (node (ref "C17") (pin "1") (pinfunction "1_1") (pintype "passive"))
      (node (ref "R14") (pin "1") (pinfunction "1_1") (pintype "passive"))
      (node (ref "R5") (pin "2") (pinfunction "2_2") (pintype "passive"))
      (node (ref "TP3") (pin "1") (pinfunction "G9_1") (pintype "passive"))
      (node (ref "U1") (pin "16") (pinfunction "2IN+_16") (pintype "input"))
    )
    (net (code "38") (name "Net-(TP8-G9)") (class "Default")
      (node (ref "C14") (pin "2") (pinfunction "2_2") (pintype "passive"))
      (node (ref "R18") (pin "1") (pinfunction "1_1") (pintype "passive"))
      (node (ref "R19") (pin "1") (pinfunction "1_1") (pintype "passive"))
      (node (ref "R8") (pin "2") (pinfunction "2_2") (pintype "passive"))
      (node (ref "TP8") (pin "1") (pinfunction "G9_1") (pintype "passive"))
      (node (ref "U1") (pin "15") (pinfunction "2IN-_15") (pintype "input"))
      (node (ref "U2") (pin "1") (pinfunction "C_1") (pintype "passive"))
      (node (ref "U2") (pin "2") (pinfunction "REF_2") (pintype "passive"))
    )
    (net (code "39") (name "Net-(TP10-G9)") (class "Default")
      (node (ref "R13") (pin "1") (pinfunction "1_1") (pintype "passive"))
      (node (ref "TP10") (pin "1") (pinfunction "G9_1") (pintype "passive"))
      (node (ref "U1") (pin "6") (pinfunction "RT_6") (pintype "passive"))
    )
    (net (code "40") (name "Net-(TP14-G9)") (class "Default")
      (node (ref "C16") (pin "1") (pinfunction "1_1") (pintype "passive"))
      (node (ref "TP14") (pin "1") (pinfunction "G9_1") (pintype "passive"))
      (node (ref "U1") (pin "5") (pinfunction "CT_5") (pintype "passive"))
    )
    (net (code "41") (name "Net-(U1-C1)") (class "Default")
      (node (ref "R7") (pin "1") (pinfunction "1_1") (pintype "passive"))
      (node (ref "U1") (pin "11") (pinfunction "C2_11") (pintype "passive"))
      (node (ref "U1") (pin "8") (pinfunction "C1_8") (pintype "passive"))
    )
    (net (code "42") (name "Net-(U1-DTC)") (class "Default")
      (node (ref "R20") (pin "2") (pinfunction "2_2") (pintype "passive"))
      (node (ref "U1") (pin "4") (pinfunction "DTC_4") (pintype "input"))
    )
    (net (code "43") (name "VCC") (class "Default")
      (node (ref "C11") (pin "2") (pinfunction "2_2") (pintype "passive"))
      (node (ref "C12") (pin "1") (pinfunction "+_1") (pintype "passive"))
      (node (ref "L1") (pin "2") (pinfunction "2_2") (pintype "passive"))
      (node (ref "P1") (pin "8") (pinfunction "8_8") (pintype "passive"))
      (node (ref "P1") (pin "9") (pinfunction "9_9") (pintype "passive"))
      (node (ref "Q1") (pin "3") (pinfunction "C_3") (pintype "passive"))
      (node (ref "Q3") (pin "3") (pinfunction "C_3") (pintype "passive"))
      (node (ref "R3") (pin "1") (pinfunction "1_1") (pintype "passive"))
      (node (ref "R4") (pin "2") (pinfunction "2_2") (pintype "passive"))
      (node (ref "R5") (pin "1") (pinfunction "1_1") (pintype "passive"))
      (node (ref "R7") (pin "2") (pinfunction "2_2") (pintype "passive"))
      (node (ref "T1") (pin "2") (pinfunction "2_2") (pintype "passive"))
      (node (ref "T1") (pin "3") (pinfunction "3_3") (pintype "passive"))
      (node (ref "TP1") (pin "1") (pinfunction "G9_1") (pintype "passive"))
      (node (ref "VD1") (pin "2") (pinfunction "A_2") (pintype "passive"))
    )
    (net (code "44") (name "unconnected-(P1-Pad5)") (class "Default")
      (node (ref "P1") (pin "5") (pinfunction "5_5") (pintype "passive"))
    )
    (net (code "45") (name "unconnected-(P1-Pad6)") (class "Default")
      (node (ref "P1") (pin "6") (pinfunction "6_6") (pintype "passive"))
    )
    (net (code "46") (name "unconnected-(P1-Pad7)") (class "Default")
      (node (ref "P1") (pin "7") (pinfunction "7_7") (pintype "passive"))
    )
    (net (code "47") (name "unconnected-(P1-Pad12)") (class "Default")
      (node (ref "P1") (pin "12") (pinfunction "12_12") (pintype "passive"))
    )
    (net (code "48") (name "unconnected-(P1-Pad13)") (class "Default")
      (node (ref "P1") (pin "13") (pinfunction "13_13") (pintype "passive"))
    )
    (net (code "49") (name "unconnected-(P1-Pad14)") (class "Default")
      (node (ref "P1") (pin "14") (pinfunction "14_14") (pintype "passive"))
    )
  )
)
